# Main.net
KiCad netlist of a schematic drawn in Altium Designer
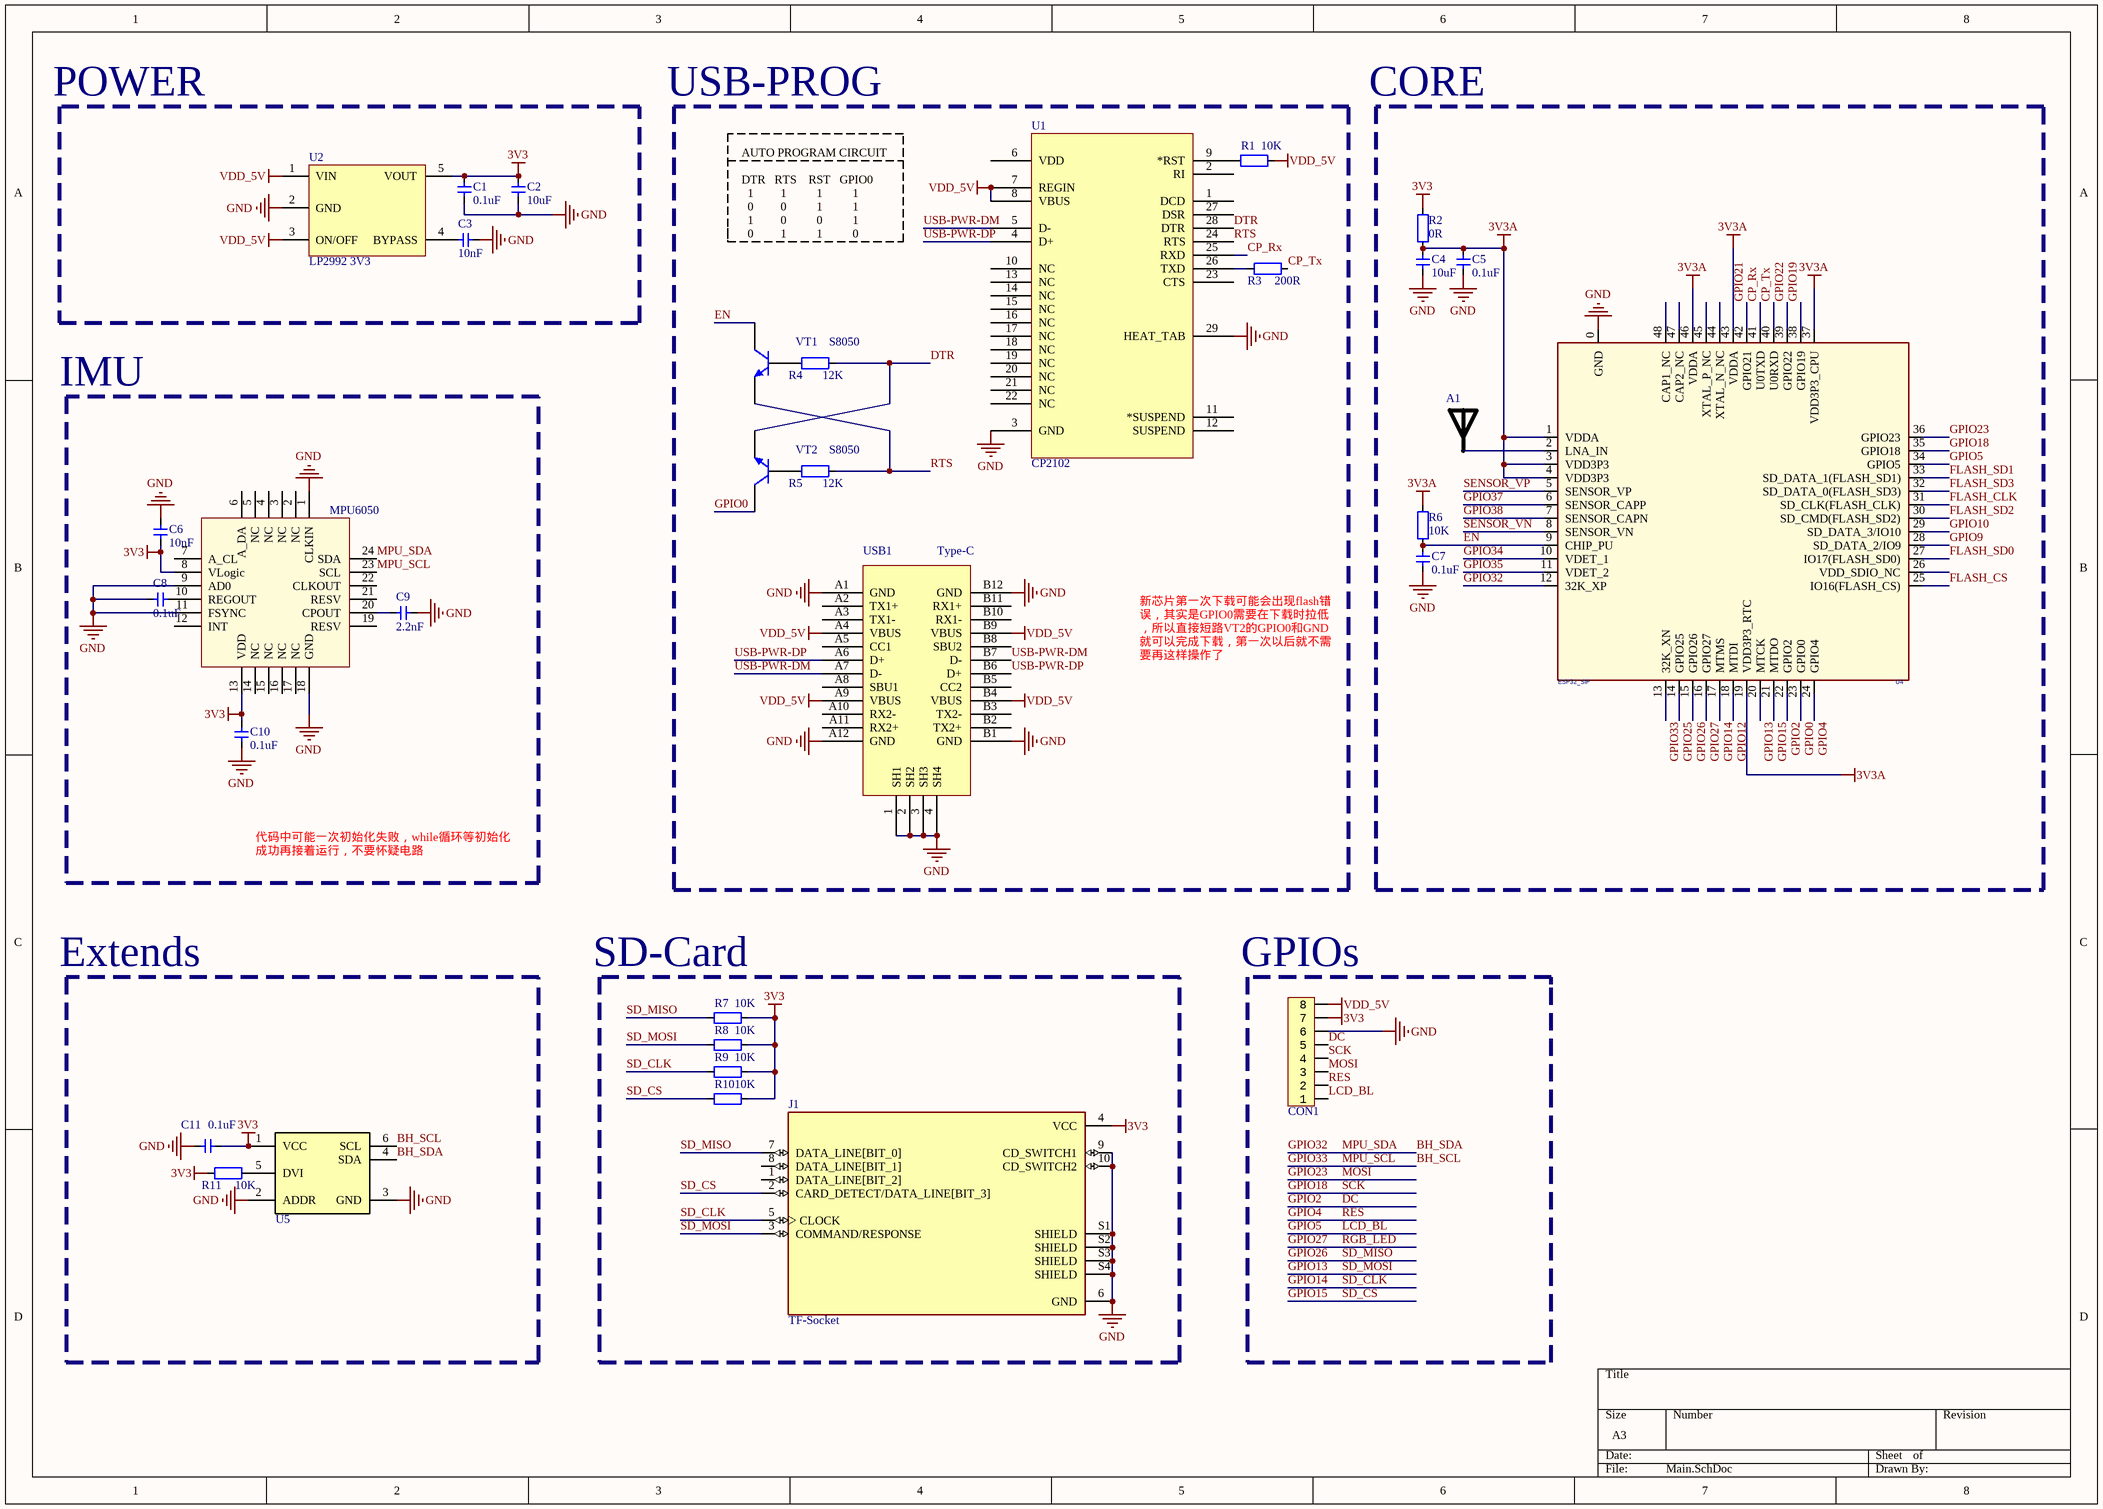
[diagram p0: Main.SchDoc]

(export (version "E")
  (design (tool "Eeschema 10.0.6"))
  (components
    (comp (ref "A1")
      (value "RAINSUN")
      (footprint "ANT-Rainsun-AN5120")
      (libsource (lib "MyPcbLib") (part "ANT-Rainsun-AP5120"))
    )
    (comp (ref "C1")
      (value "0.1uF")
      (footprint "CAP_0402")
      (description "Capacitor")
      (libsource (lib "MyPcbLib") (part "电容-0402"))
    )
    (comp (ref "C2")
      (value "10uF")
      (footprint "CAP_0402")
      (description "Capacitor")
      (libsource (lib "MyPcbLib") (part "电容-0402"))
    )
    (comp (ref "C3")
      (value "10nF")
      (footprint "CAP_0402")
      (description "Capacitor")
      (libsource (lib "MyPcbLib") (part "电容-0402"))
    )
    (comp (ref "C4")
      (value "10uF")
      (footprint "CAP_0402")
      (description "Capacitor")
      (libsource (lib "MyPcbLib") (part "电容-0402"))
    )
    (comp (ref "C5")
      (value "0.1uF")
      (footprint "CAP_0402")
      (description "Capacitor")
      (libsource (lib "MyPcbLib") (part "电容-0402"))
    )
    (comp (ref "C6")
      (value "10nF")
      (footprint "CAP_0402")
      (description "Capacitor")
      (libsource (lib "MyPcbLib") (part "电容-0402"))
    )
    (comp (ref "C7")
      (value "0.1uF")
      (footprint "CAP_0402")
      (description "Capacitor")
      (libsource (lib "MyPcbLib") (part "电容-0402"))
    )
    (comp (ref "C8")
      (value "0.1uF")
      (footprint "CAP_0402")
      (description "Capacitor")
      (libsource (lib "MyPcbLib") (part "电容-0402"))
    )
    (comp (ref "C9")
      (value "2.2nF")
      (footprint "CAP_0402")
      (description "Capacitor")
      (libsource (lib "MyPcbLib") (part "电容-0402"))
    )
    (comp (ref "C10")
      (value "0.1uF")
      (footprint "CAP_0402")
      (description "Capacitor")
      (libsource (lib "MyPcbLib") (part "电容-0402"))
    )
    (comp (ref "C11")
      (value "0.1uF")
      (footprint "CAP_0402")
      (description "Capacitor")
      (libsource (lib "MyPcbLib") (part "电容-0402"))
    )
    (comp (ref "CON1")
      (value "FFC_0.5_8")
      (footprint "FFC_0.5_8")
      (description "FFC")
      (libsource (lib "KitSprout") (part "FFC_0.5_8"))
    )
    (comp (ref "J1")
      (value "TF-Socket")
      (footprint "TF-Card-Amphenol with TF")
      (description "10 _8 + 2_ Position Card Connector Secure Digital - microSDâ„¢ Surface Mount, Right Angle Gold")
      (fields (field (name "MP") "1140084168") (field (name "MF") "Amphenol Commercial Products"))
      (libsource (lib "MyPcbLib") (part "TF-Socket"))
    )
    (comp (ref "R1")
      (value "10K")
      (footprint "RES_0402")
      (description "Resistor")
      (libsource (lib "MyPcbLib") (part "电阻-0402"))
    )
    (comp (ref "R2")
      (value "0R")
      (footprint "RES_0402")
      (description "Resistor")
      (libsource (lib "") (part "电阻-0402_1"))
    )
    (comp (ref "R3")
      (value "200R")
      (footprint "RES_0402")
      (description "Resistor")
      (libsource (lib "MyPcbLib") (part "电阻-0402"))
    )
    (comp (ref "R4")
      (value "12K")
      (footprint "RES_0402")
      (description "Resistor")
      (libsource (lib "MyPcbLib") (part "电阻-0402"))
    )
    (comp (ref "R5")
      (value "12K")
      (footprint "RES_0402")
      (description "Resistor")
      (libsource (lib "MyPcbLib") (part "电阻-0402"))
    )
    (comp (ref "R6")
      (value "10K")
      (footprint "RES_0402")
      (description "Resistor")
      (libsource (lib "") (part "电阻-0402_1"))
    )
    (comp (ref "R7")
      (value "10K")
      (footprint "RES_0402")
      (description "Resistor")
      (libsource (lib "MyPcbLib") (part "电阻-0402"))
    )
    (comp (ref "R8")
      (value "10K")
      (footprint "RES_0402")
      (description "Resistor")
      (libsource (lib "MyPcbLib") (part "电阻-0402"))
    )
    (comp (ref "R9")
      (value "10K")
      (footprint "RES_0402")
      (description "Resistor")
      (libsource (lib "MyPcbLib") (part "电阻-0402"))
    )
    (comp (ref "R10")
      (value "10K")
      (footprint "RES_0402")
      (description "Resistor")
      (libsource (lib "MyPcbLib") (part "电阻-0402"))
    )
    (comp (ref "R11")
      (value "10K")
      (footprint "RES_0402")
      (description "Resistor")
      (libsource (lib "MyPcbLib") (part "电阻-0402"))
    )
    (comp (ref "U1")
      (value "CP2102")
      (footprint "QFN-28")
      (description "USB转TTL")
      (libsource (lib "mLib") (part "CP2102"))
    )
    (comp (ref "U2")
      (value "LP2992 3V3")
      (footprint "SOT23-5")
      (description "LDO")
      (libsource (lib "MyPcbLib") (part "LP2992"))
    )
    (comp (ref "U3")
      (value "MPU6050")
      (footprint "QFN-24")
      (description "六轴传感器")
      (libsource (lib "mLib") (part "MPU6050"))
    )
    (comp (ref "U4")
      (value "ESP32_SIP")
      (footprint "QFN-48_7X7")
      (libsource (lib "MyPcbLib") (part "ESP32-PICO"))
    )
    (comp (ref "U5")
      (value "BH1750FVI-TR")
      (footprint "BH1750FVI")
      (libsource (lib "MyPcbLib") (part "BH1750FVI-TR"))
    )
    (comp (ref "USB1")
      (value "Type-C")
      (footprint "Type-C-TOP")
      (libsource (lib "MyPcbLib") (part "USB-Type-C-TOP"))
    )
    (comp (ref "VT1")
      (value "S8050")
      (footprint "SMT_TRIODE_NPN")
      (description "Surface mount NPN transistor, package SOT-23")
      (libsource (lib "MyPcbLib") (part "SMT_TRIODE_NPN"))
    )
    (comp (ref "VT2")
      (value "S8050")
      (footprint "SMT_TRIODE_NPN")
      (description "Surface mount NPN transistor, package SOT-23")
      (libsource (lib "MyPcbLib") (part "SMT_TRIODE_NPN"))
    )
  )
  (nets
    (net (code "1") (name "/BH_SCL") (class "Default")
      (node (ref "U3") (pin "23") (pinfunction "SCL_23") (pintype "passive"))
      (node (ref "U4") (pin "13") (pinfunction "32K_XN_13") (pintype "passive"))
      (node (ref "U5") (pin "6") (pinfunction "SCL_6") (pintype "passive"))
    )
    (net (code "2") (name "/BH_SDA") (class "Default")
      (node (ref "U3") (pin "24") (pinfunction "SDA_24") (pintype "passive"))
      (node (ref "U4") (pin "12") (pinfunction "32K_XP_12") (pintype "passive"))
      (node (ref "U5") (pin "4") (pinfunction "SDA_4") (pintype "passive"))
    )
    (net (code "3") (name "/CP_Rx") (class "Default")
      (node (ref "U1") (pin "25") (pinfunction "RXD_25") (pintype "passive"))
      (node (ref "U4") (pin "41") (pinfunction "U0TXD_41") (pintype "power_in"))
    )
    (net (code "4") (name "/CP_Tx") (class "Default")
      (node (ref "R3") (pin "1") (pinfunction "1_1") (pintype "passive"))
      (node (ref "U4") (pin "40") (pinfunction "U0RXD_40") (pintype "power_in"))
    )
    (net (code "5") (name "/DC") (class "Default")
      (node (ref "CON1") (pin "5") (pinfunction "5_5") (pintype "passive"))
      (node (ref "U4") (pin "22") (pinfunction "GPIO2_22") (pintype "passive"))
    )
    (net (code "6") (name "/DTR") (class "Default")
      (node (ref "R4") (pin "1") (pinfunction "1_1") (pintype "passive"))
      (node (ref "U1") (pin "28") (pinfunction "DTR_28") (pintype "passive"))
      (node (ref "VT2") (pin "2") (pinfunction "E_2") (pintype "passive"))
    )
    (net (code "7") (name "/EN") (class "Default")
      (node (ref "C7") (pin "1") (pinfunction "1_1") (pintype "passive"))
      (node (ref "R6") (pin "2") (pinfunction "2_2") (pintype "passive"))
      (node (ref "U4") (pin "9") (pinfunction "CHIP_PU_9") (pintype "passive"))
      (node (ref "VT1") (pin "3") (pinfunction "C_3") (pintype "passive"))
    )
    (net (code "8") (name "/FLASH_CLK") (class "Default")
      (node (ref "U4") (pin "31") (pinfunction "SD_CLK(FLASH_CLK)_31") (pintype "passive"))
    )
    (net (code "9") (name "/FLASH_CS") (class "Default")
      (node (ref "U4") (pin "25") (pinfunction "IO16(FLASH_CS)_25") (pintype "passive"))
    )
    (net (code "10") (name "/FLASH_SD0") (class "Default")
      (node (ref "U4") (pin "27") (pinfunction "IO17(FLASH_SD0)_27") (pintype "passive"))
    )
    (net (code "11") (name "/FLASH_SD1") (class "Default")
      (node (ref "U4") (pin "33") (pinfunction "SD_DATA_1(FLASH_SD1)_33") (pintype "passive"))
    )
    (net (code "12") (name "/FLASH_SD2") (class "Default")
      (node (ref "U4") (pin "30") (pinfunction "SD_CMD(FLASH_SD2)_30") (pintype "passive"))
    )
    (net (code "13") (name "/FLASH_SD3") (class "Default")
      (node (ref "U4") (pin "32") (pinfunction "SD_DATA_0(FLASH_SD3)_32") (pintype "passive"))
    )
    (net (code "14") (name "/GPIO0") (class "Default")
      (node (ref "U4") (pin "23") (pinfunction "GPIO0_23") (pintype "passive"))
      (node (ref "VT2") (pin "3") (pinfunction "C_3") (pintype "passive"))
    )
    (net (code "15") (name "/GPIO4") (class "Default")
      (node (ref "CON1") (pin "2") (pinfunction "2_2") (pintype "passive"))
      (node (ref "U4") (pin "24") (pinfunction "GPIO4_24") (pintype "passive"))
    )
    (net (code "16") (name "/GPIO5") (class "Default")
      (node (ref "CON1") (pin "1") (pinfunction "1_1") (pintype "passive"))
      (node (ref "U4") (pin "34") (pinfunction "GPIO5_34") (pintype "passive"))
    )
    (net (code "17") (name "/GPIO9") (class "Default")
      (node (ref "U4") (pin "28") (pinfunction "SD_DATA_2/IO9_28") (pintype "passive"))
    )
    (net (code "18") (name "/GPIO10") (class "Default")
      (node (ref "U4") (pin "29") (pinfunction "SD_DATA_3/IO10_29") (pintype "passive"))
    )
    (net (code "19") (name "/GPIO12") (class "Default")
      (node (ref "U4") (pin "18") (pinfunction "MTDI_18") (pintype "passive"))
    )
    (net (code "20") (name "/GPIO13") (class "Default")
      (node (ref "J1") (pin "3") (pinfunction "COMMAND/RESPONSE_3") (pintype "bidirectional"))
      (node (ref "R8") (pin "2") (pinfunction "2_2") (pintype "passive"))
      (node (ref "U4") (pin "20") (pinfunction "MTCK_20") (pintype "passive"))
    )
    (net (code "21") (name "/GPIO14") (class "Default")
      (node (ref "J1") (pin "5") (pinfunction "CLOCK_5") (pintype "bidirectional"))
      (node (ref "R9") (pin "2") (pinfunction "2_2") (pintype "passive"))
      (node (ref "U4") (pin "17") (pinfunction "MTMS_17") (pintype "passive"))
    )
    (net (code "22") (name "/GPIO15") (class "Default")
      (node (ref "J1") (pin "2") (pinfunction "CARD_DETECT/DATA_LINE[BIT_3]_2") (pintype "bidirectional"))
      (node (ref "R10") (pin "2") (pinfunction "2_2") (pintype "passive"))
      (node (ref "U4") (pin "21") (pinfunction "MTDO_21") (pintype "passive"))
    )
    (net (code "23") (name "/GPIO18") (class "Default")
      (node (ref "CON1") (pin "4") (pinfunction "4_4") (pintype "passive"))
      (node (ref "U4") (pin "35") (pinfunction "GPIO18_35") (pintype "passive"))
    )
    (net (code "24") (name "/GPIO19") (class "Default")
      (node (ref "U4") (pin "38") (pinfunction "GPIO19_38") (pintype "passive"))
    )
    (net (code "25") (name "/GPIO21") (class "Default")
      (node (ref "U4") (pin "42") (pinfunction "GPIO21_42") (pintype "passive"))
    )
    (net (code "26") (name "/GPIO22") (class "Default")
      (node (ref "U4") (pin "39") (pinfunction "GPIO22_39") (pintype "passive"))
    )
    (net (code "27") (name "/GPIO23") (class "Default")
      (node (ref "CON1") (pin "3") (pinfunction "3_3") (pintype "passive"))
      (node (ref "U4") (pin "36") (pinfunction "GPIO23_36") (pintype "passive"))
    )
    (net (code "28") (name "/GPIO25") (class "Default")
      (node (ref "U4") (pin "14") (pinfunction "GPIO25_14") (pintype "passive"))
    )
    (net (code "29") (name "/GPIO26") (class "Default")
      (node (ref "J1") (pin "7") (pinfunction "DATA_LINE[BIT_0]_7") (pintype "bidirectional"))
      (node (ref "R7") (pin "2") (pinfunction "2_2") (pintype "passive"))
      (node (ref "U4") (pin "15") (pinfunction "GPIO26_15") (pintype "passive"))
    )
    (net (code "30") (name "/GPIO27") (class "Default")
      (node (ref "U4") (pin "16") (pinfunction "GPIO27_16") (pintype "passive"))
    )
    (net (code "31") (name "/GPIO34") (class "Default")
      (node (ref "U4") (pin "10") (pinfunction "VDET_1_10") (pintype "passive"))
    )
    (net (code "32") (name "/GPIO35") (class "Default")
      (node (ref "U4") (pin "11") (pinfunction "VDET_2_11") (pintype "passive"))
    )
    (net (code "33") (name "/GPIO37") (class "Default")
      (node (ref "U4") (pin "6") (pinfunction "SENSOR_CAPP_6") (pintype "passive"))
    )
    (net (code "34") (name "/GPIO38") (class "Default")
      (node (ref "U4") (pin "7") (pinfunction "SENSOR_CAPN_7") (pintype "passive"))
    )
    (net (code "35") (name "/RTS") (class "Default")
      (node (ref "R5") (pin "1") (pinfunction "1_1") (pintype "passive"))
      (node (ref "U1") (pin "24") (pinfunction "RTS_24") (pintype "passive"))
      (node (ref "VT1") (pin "2") (pinfunction "E_2") (pintype "passive"))
    )
    (net (code "36") (name "/SENSOR_VN") (class "Default")
      (node (ref "U4") (pin "8") (pinfunction "SENSOR_VN_8") (pintype "passive"))
    )
    (net (code "37") (name "/SENSOR_VP") (class "Default")
      (node (ref "U4") (pin "5") (pinfunction "SENSOR_VP_5") (pintype "passive"))
    )
    (net (code "38") (name "/USB-PWR-DM") (class "Default")
      (node (ref "U1") (pin "5") (pinfunction "D-_5") (pintype "passive"))
      (node (ref "USB1") (pin "A7") (pinfunction "D-_A7") (pintype "passive"))
      (node (ref "USB1") (pin "B7") (pinfunction "D-_B7") (pintype "passive"))
    )
    (net (code "39") (name "/USB-PWR-DP") (class "Default")
      (node (ref "U1") (pin "4") (pinfunction "D+_4") (pintype "passive"))
      (node (ref "USB1") (pin "A6") (pinfunction "D+_A6") (pintype "passive"))
      (node (ref "USB1") (pin "B6") (pinfunction "D+_B6") (pintype "passive"))
    )
    (net (code "40") (name "3V3") (class "Default")
      (node (ref "C1") (pin "2") (pinfunction "2_2") (pintype "passive"))
      (node (ref "C10") (pin "2") (pinfunction "2_2") (pintype "passive"))
      (node (ref "C11") (pin "1") (pinfunction "1_1") (pintype "passive"))
      (node (ref "C2") (pin "2") (pinfunction "2_2") (pintype "passive"))
      (node (ref "C6") (pin "1") (pinfunction "1_1") (pintype "passive"))
      (node (ref "CON1") (pin "7") (pinfunction "7_7") (pintype "passive"))
      (node (ref "J1") (pin "4") (pinfunction "VCC_4") (pintype "power_in"))
      (node (ref "R10") (pin "1") (pinfunction "1_1") (pintype "passive"))
      (node (ref "R11") (pin "2") (pinfunction "2_2") (pintype "passive"))
      (node (ref "R2") (pin "1") (pinfunction "1_1") (pintype "passive"))
      (node (ref "R7") (pin "1") (pinfunction "1_1") (pintype "passive"))
      (node (ref "R8") (pin "1") (pinfunction "1_1") (pintype "passive"))
      (node (ref "R9") (pin "1") (pinfunction "1_1") (pintype "passive"))
      (node (ref "U2") (pin "5") (pinfunction "VOUT_5") (pintype "passive"))
      (node (ref "U3") (pin "13") (pinfunction "VDD_13") (pintype "passive"))
      (node (ref "U3") (pin "8") (pinfunction "VLogic_8") (pintype "passive"))
      (node (ref "U5") (pin "1") (pinfunction "VCC_1") (pintype "passive"))
    )
    (net (code "41") (name "3V3A") (class "Default")
      (node (ref "C4") (pin "2") (pinfunction "2_2") (pintype "passive"))
      (node (ref "C5") (pin "2") (pinfunction "2_2") (pintype "passive"))
      (node (ref "R2") (pin "2") (pinfunction "2_2") (pintype "passive"))
      (node (ref "R6") (pin "1") (pinfunction "1_1") (pintype "passive"))
      (node (ref "U4") (pin "1") (pinfunction "VDDA_1") (pintype "power_in"))
      (node (ref "U4") (pin "19") (pinfunction "VDD3P3_RTC_19") (pintype "power_in"))
      (node (ref "U4") (pin "3") (pinfunction "VDD3P3_3") (pintype "power_in"))
      (node (ref "U4") (pin "37") (pinfunction "VDD3P3_CPU_37") (pintype "power_in"))
      (node (ref "U4") (pin "4") (pinfunction "VDD3P3_4") (pintype "power_in"))
      (node (ref "U4") (pin "43") (pinfunction "VDDA_43") (pintype "power_in"))
      (node (ref "U4") (pin "46") (pinfunction "VDDA_46") (pintype "power_in"))
    )
    (net (code "42") (name "GND") (class "Default")
      (node (ref "C1") (pin "1") (pinfunction "1_1") (pintype "passive"))
      (node (ref "C10") (pin "1") (pinfunction "1_1") (pintype "passive"))
      (node (ref "C11") (pin "2") (pinfunction "2_2") (pintype "passive"))
      (node (ref "C2") (pin "1") (pinfunction "1_1") (pintype "passive"))
      (node (ref "C3") (pin "1") (pinfunction "1_1") (pintype "passive"))
      (node (ref "C4") (pin "1") (pinfunction "1_1") (pintype "passive"))
      (node (ref "C5") (pin "1") (pinfunction "1_1") (pintype "passive"))
      (node (ref "C6") (pin "2") (pinfunction "2_2") (pintype "passive"))
      (node (ref "C7") (pin "2") (pinfunction "2_2") (pintype "passive"))
      (node (ref "C8") (pin "2") (pinfunction "2_2") (pintype "passive"))
      (node (ref "C9") (pin "1") (pinfunction "1_1") (pintype "passive"))
      (node (ref "CON1") (pin "6") (pinfunction "6_6") (pintype "passive"))
      (node (ref "J1") (pin "10") (pinfunction "CD_SWITCH2_10") (pintype "bidirectional"))
      (node (ref "J1") (pin "6") (pinfunction "GND_6") (pintype "power_in"))
      (node (ref "J1") (pin "9") (pinfunction "CD_SWITCH1_9") (pintype "bidirectional"))
      (node (ref "J1") (pin "S1") (pinfunction "SHIELD_S1") (pintype "passive"))
      (node (ref "J1") (pin "S2") (pinfunction "SHIELD_S2") (pintype "passive"))
      (node (ref "J1") (pin "S3") (pinfunction "SHIELD_S3") (pintype "passive"))
      (node (ref "J1") (pin "S4") (pinfunction "SHIELD_S4") (pintype "passive"))
      (node (ref "U1") (pin "29") (pinfunction "HEAT_TAB_29") (pintype "passive"))
      (node (ref "U1") (pin "3") (pinfunction "GND_3") (pintype "passive"))
      (node (ref "U2") (pin "2") (pinfunction "GND_2") (pintype "passive"))
      (node (ref "U3") (pin "1") (pinfunction "CLKIN_1") (pintype "passive"))
      (node (ref "U3") (pin "11") (pinfunction "FSYNC_11") (pintype "passive"))
      (node (ref "U3") (pin "18") (pinfunction "GND_18") (pintype "passive"))
      (node (ref "U3") (pin "9") (pinfunction "AD0_9") (pintype "passive"))
      (node (ref "U4") (pin "0") (pinfunction "GND_0") (pintype "power_in"))
      (node (ref "U5") (pin "2") (pinfunction "ADDR_2") (pintype "passive"))
      (node (ref "U5") (pin "3") (pinfunction "GND_3") (pintype "passive"))
      (node (ref "USB1") (pin "1") (pinfunction "SH1_1") (pintype "passive"))
      (node (ref "USB1") (pin "2") (pinfunction "SH2_2") (pintype "passive"))
      (node (ref "USB1") (pin "3") (pinfunction "SH3_3") (pintype "passive"))
      (node (ref "USB1") (pin "4") (pinfunction "SH4_4") (pintype "passive"))
      (node (ref "USB1") (pin "A1") (pinfunction "GND_A1") (pintype "passive"))
      (node (ref "USB1") (pin "A12") (pinfunction "GND_A12") (pintype "passive"))
      (node (ref "USB1") (pin "B1") (pinfunction "GND_B1") (pintype "passive"))
      (node (ref "USB1") (pin "B12") (pinfunction "GND_B12") (pintype "passive"))
    )
    (net (code "43") (name "Net-(U1-*RST)") (class "Default")
      (node (ref "R1") (pin "2") (pinfunction "2_2") (pintype "passive"))
      (node (ref "U1") (pin "9") (pinfunction "*RST_9") (pintype "passive"))
    )
    (net (code "44") (name "Net-(U1-TXD)") (class "Default")
      (node (ref "R3") (pin "2") (pinfunction "2_2") (pintype "passive"))
      (node (ref "U1") (pin "26") (pinfunction "TXD_26") (pintype "passive"))
    )
    (net (code "45") (name "Net-(U2-BYPASS)") (class "Default")
      (node (ref "C3") (pin "2") (pinfunction "2_2") (pintype "passive"))
      (node (ref "U2") (pin "4") (pinfunction "BYPASS_4") (pintype "passive"))
    )
    (net (code "46") (name "Net-(U3-CPOUT)") (class "Default")
      (node (ref "C9") (pin "2") (pinfunction "2_2") (pintype "passive"))
      (node (ref "U3") (pin "20") (pinfunction "CPOUT_20") (pintype "passive"))
    )
    (net (code "47") (name "Net-(U3-REGOUT)") (class "Default")
      (node (ref "C8") (pin "1") (pinfunction "1_1") (pintype "passive"))
      (node (ref "U3") (pin "10") (pinfunction "REGOUT_10") (pintype "passive"))
    )
    (net (code "48") (name "Net-(U4-LNA_IN)") (class "Default")
      (node (ref "A1") (pin "1") (pinfunction "1_1") (pintype "passive"))
      (node (ref "U4") (pin "2") (pinfunction "LNA_IN_2") (pintype "passive"))
    )
    (net (code "49") (name "Net-(U5-DVI)") (class "Default")
      (node (ref "R11") (pin "1") (pinfunction "1_1") (pintype "passive"))
      (node (ref "U5") (pin "5") (pinfunction "DVI_5") (pintype "passive"))
    )
    (net (code "50") (name "Net-(VT1-B)") (class "Default")
      (node (ref "R4") (pin "2") (pinfunction "2_2") (pintype "passive"))
      (node (ref "VT1") (pin "1") (pinfunction "B_1") (pintype "passive"))
    )
    (net (code "51") (name "Net-(VT2-B)") (class "Default")
      (node (ref "R5") (pin "2") (pinfunction "2_2") (pintype "passive"))
      (node (ref "VT2") (pin "1") (pinfunction "B_1") (pintype "passive"))
    )
    (net (code "52") (name "VDD_5V") (class "Default")
      (node (ref "CON1") (pin "8") (pinfunction "8_8") (pintype "passive"))
      (node (ref "R1") (pin "1") (pinfunction "1_1") (pintype "passive"))
      (node (ref "U1") (pin "7") (pinfunction "REGIN_7") (pintype "passive"))
      (node (ref "U1") (pin "8") (pinfunction "VBUS_8") (pintype "passive"))
      (node (ref "U2") (pin "1") (pinfunction "VIN_1") (pintype "passive"))
      (node (ref "U2") (pin "3") (pinfunction "ON/OFF_3") (pintype "passive"))
      (node (ref "USB1") (pin "A4") (pinfunction "VBUS_A4") (pintype "passive"))
      (node (ref "USB1") (pin "A9") (pinfunction "VBUS_A9") (pintype "passive"))
      (node (ref "USB1") (pin "B4") (pinfunction "VBUS_B4") (pintype "passive"))
      (node (ref "USB1") (pin "B9") (pinfunction "VBUS_B9") (pintype "passive"))
    )
    (net (code "53") (name "unconnected-(J1-DATA_LINE[BIT_1]-Pad8)") (class "Default")
      (node (ref "J1") (pin "8") (pinfunction "DATA_LINE[BIT_1]_8") (pintype "bidirectional"))
    )
    (net (code "54") (name "unconnected-(J1-DATA_LINE[BIT_2]-Pad1)") (class "Default")
      (node (ref "J1") (pin "1") (pinfunction "DATA_LINE[BIT_2]_1") (pintype "bidirectional"))
    )
    (net (code "55") (name "unconnected-(U1-*SUSPEND-Pad11)") (class "Default")
      (node (ref "U1") (pin "11") (pinfunction "*SUSPEND_11") (pintype "passive"))
    )
    (net (code "56") (name "unconnected-(U1-CTS-Pad23)") (class "Default")
      (node (ref "U1") (pin "23") (pinfunction "CTS_23") (pintype "passive"))
    )
    (net (code "57") (name "unconnected-(U1-DCD-Pad1)") (class "Default")
      (node (ref "U1") (pin "1") (pinfunction "DCD_1") (pintype "passive"))
    )
    (net (code "58") (name "unconnected-(U1-DSR-Pad27)") (class "Default")
      (node (ref "U1") (pin "27") (pinfunction "DSR_27") (pintype "passive"))
    )
    (net (code "59") (name "unconnected-(U1-NC-Pad10)") (class "Default")
      (node (ref "U1") (pin "10") (pinfunction "NC_10") (pintype "passive"))
    )
    (net (code "60") (name "unconnected-(U1-NC-Pad13)") (class "Default")
      (node (ref "U1") (pin "13") (pinfunction "NC_13") (pintype "passive"))
    )
    (net (code "61") (name "unconnected-(U1-NC-Pad14)") (class "Default")
      (node (ref "U1") (pin "14") (pinfunction "NC_14") (pintype "passive"))
    )
    (net (code "62") (name "unconnected-(U1-NC-Pad15)") (class "Default")
      (node (ref "U1") (pin "15") (pinfunction "NC_15") (pintype "passive"))
    )
    (net (code "63") (name "unconnected-(U1-NC-Pad16)") (class "Default")
      (node (ref "U1") (pin "16") (pinfunction "NC_16") (pintype "passive"))
    )
    (net (code "64") (name "unconnected-(U1-NC-Pad17)") (class "Default")
      (node (ref "U1") (pin "17") (pinfunction "NC_17") (pintype "passive"))
    )
    (net (code "65") (name "unconnected-(U1-NC-Pad18)") (class "Default")
      (node (ref "U1") (pin "18") (pinfunction "NC_18") (pintype "passive"))
    )
    (net (code "66") (name "unconnected-(U1-NC-Pad19)") (class "Default")
      (node (ref "U1") (pin "19") (pinfunction "NC_19") (pintype "passive"))
    )
    (net (code "67") (name "unconnected-(U1-NC-Pad20)") (class "Default")
      (node (ref "U1") (pin "20") (pinfunction "NC_20") (pintype "passive"))
    )
    (net (code "68") (name "unconnected-(U1-NC-Pad21)") (class "Default")
      (node (ref "U1") (pin "21") (pinfunction "NC_21") (pintype "passive"))
    )
    (net (code "69") (name "unconnected-(U1-NC-Pad22)") (class "Default")
      (node (ref "U1") (pin "22") (pinfunction "NC_22") (pintype "passive"))
    )
    (net (code "70") (name "unconnected-(U1-RI-Pad2)") (class "Default")
      (node (ref "U1") (pin "2") (pinfunction "RI_2") (pintype "passive"))
    )
    (net (code "71") (name "unconnected-(U1-SUSPEND-Pad12)") (class "Default")
      (node (ref "U1") (pin "12") (pinfunction "SUSPEND_12") (pintype "passive"))
    )
    (net (code "72") (name "unconnected-(U1-VDD-Pad6)") (class "Default")
      (node (ref "U1") (pin "6") (pinfunction "VDD_6") (pintype "passive"))
    )
    (net (code "73") (name "unconnected-(U3-A_CL-Pad7)") (class "Default")
      (node (ref "U3") (pin "7") (pinfunction "A_CL_7") (pintype "passive"))
    )
    (net (code "74") (name "unconnected-(U3-A_DA-Pad6)") (class "Default")
      (node (ref "U3") (pin "6") (pinfunction "A_DA_6") (pintype "passive"))
    )
    (net (code "75") (name "unconnected-(U3-CLKOUT-Pad22)") (class "Default")
      (node (ref "U3") (pin "22") (pinfunction "CLKOUT_22") (pintype "passive"))
    )
    (net (code "76") (name "unconnected-(U3-INT-Pad12)") (class "Default")
      (node (ref "U3") (pin "12") (pinfunction "INT_12") (pintype "passive"))
    )
    (net (code "77") (name "unconnected-(U3-NC-Pad2)") (class "Default")
      (node (ref "U3") (pin "2") (pinfunction "NC_2") (pintype "passive"))
    )
    (net (code "78") (name "unconnected-(U3-NC-Pad3)") (class "Default")
      (node (ref "U3") (pin "3") (pinfunction "NC_3") (pintype "passive"))
    )
    (net (code "79") (name "unconnected-(U3-NC-Pad4)") (class "Default")
      (node (ref "U3") (pin "4") (pinfunction "NC_4") (pintype "passive"))
    )
    (net (code "80") (name "unconnected-(U3-NC-Pad5)") (class "Default")
      (node (ref "U3") (pin "5") (pinfunction "NC_5") (pintype "passive"))
    )
    (net (code "81") (name "unconnected-(U3-NC-Pad14)") (class "Default")
      (node (ref "U3") (pin "14") (pinfunction "NC_14") (pintype "passive"))
    )
    (net (code "82") (name "unconnected-(U3-NC-Pad15)") (class "Default")
      (node (ref "U3") (pin "15") (pinfunction "NC_15") (pintype "passive"))
    )
    (net (code "83") (name "unconnected-(U3-NC-Pad16)") (class "Default")
      (node (ref "U3") (pin "16") (pinfunction "NC_16") (pintype "passive"))
    )
    (net (code "84") (name "unconnected-(U3-NC-Pad17)") (class "Default")
      (node (ref "U3") (pin "17") (pinfunction "NC_17") (pintype "passive"))
    )
    (net (code "85") (name "unconnected-(U3-RESV-Pad19)") (class "Default")
      (node (ref "U3") (pin "19") (pinfunction "RESV_19") (pintype "passive"))
    )
    (net (code "86") (name "unconnected-(U3-RESV-Pad21)") (class "Default")
      (node (ref "U3") (pin "21") (pinfunction "RESV_21") (pintype "passive"))
    )
    (net (code "87") (name "unconnected-(U4-CAP1_NC-Pad48)") (class "Default")
      (node (ref "U4") (pin "48") (pinfunction "CAP1_NC_48") (pintype "passive"))
    )
    (net (code "88") (name "unconnected-(U4-CAP2_NC-Pad47)") (class "Default")
      (node (ref "U4") (pin "47") (pinfunction "CAP2_NC_47") (pintype "passive"))
    )
    (net (code "89") (name "unconnected-(U4-VDD_SDIO_NC-Pad26)") (class "Default")
      (node (ref "U4") (pin "26") (pinfunction "VDD_SDIO_NC_26") (pintype "passive"))
    )
    (net (code "90") (name "unconnected-(U4-XTAL_N_NC-Pad44)") (class "Default")
      (node (ref "U4") (pin "44") (pinfunction "XTAL_N_NC_44") (pintype "passive"))
    )
    (net (code "91") (name "unconnected-(U4-XTAL_P_NC-Pad45)") (class "Default")
      (node (ref "U4") (pin "45") (pinfunction "XTAL_P_NC_45") (pintype "passive"))
    )
    (net (code "92") (name "unconnected-(USB1-CC1-PadA5)") (class "Default")
      (node (ref "USB1") (pin "A5") (pinfunction "CC1_A5") (pintype "passive"))
    )
    (net (code "93") (name "unconnected-(USB1-CC2-PadB5)") (class "Default")
      (node (ref "USB1") (pin "B5") (pinfunction "CC2_B5") (pintype "passive"))
    )
    (net (code "94") (name "unconnected-(USB1-RX1+-PadB11)") (class "Default")
      (node (ref "USB1") (pin "B11") (pinfunction "RX1+_B11") (pintype "passive"))
    )
    (net (code "95") (name "unconnected-(USB1-RX1--PadB10)") (class "Default")
      (node (ref "USB1") (pin "B10") (pinfunction "RX1-_B10") (pintype "passive"))
    )
    (net (code "96") (name "unconnected-(USB1-RX2+-PadA11)") (class "Default")
      (node (ref "USB1") (pin "A11") (pinfunction "RX2+_A11") (pintype "passive"))
    )
    (net (code "97") (name "unconnected-(USB1-RX2--PadA10)") (class "Default")
      (node (ref "USB1") (pin "A10") (pinfunction "RX2-_A10") (pintype "passive"))
    )
    (net (code "98") (name "unconnected-(USB1-SBU1-PadA8)") (class "Default")
      (node (ref "USB1") (pin "A8") (pinfunction "SBU1_A8") (pintype "passive"))
    )
    (net (code "99") (name "unconnected-(USB1-SBU2-PadB8)") (class "Default")
      (node (ref "USB1") (pin "B8") (pinfunction "SBU2_B8") (pintype "passive"))
    )
    (net (code "100") (name "unconnected-(USB1-TX1+-PadA2)") (class "Default")
      (node (ref "USB1") (pin "A2") (pinfunction "TX1+_A2") (pintype "passive"))
    )
    (net (code "101") (name "unconnected-(USB1-TX1--PadA3)") (class "Default")
      (node (ref "USB1") (pin "A3") (pinfunction "TX1-_A3") (pintype "passive"))
    )
    (net (code "102") (name "unconnected-(USB1-TX2+-PadB2)") (class "Default")
      (node (ref "USB1") (pin "B2") (pinfunction "TX2+_B2") (pintype "passive"))
    )
    (net (code "103") (name "unconnected-(USB1-TX2--PadB3)") (class "Default")
      (node (ref "USB1") (pin "B3") (pinfunction "TX2-_B3") (pintype "passive"))
    )
  )
)
